# LMP2011basedV2.net
KiCad netlist of a schematic drawn in EAGLE
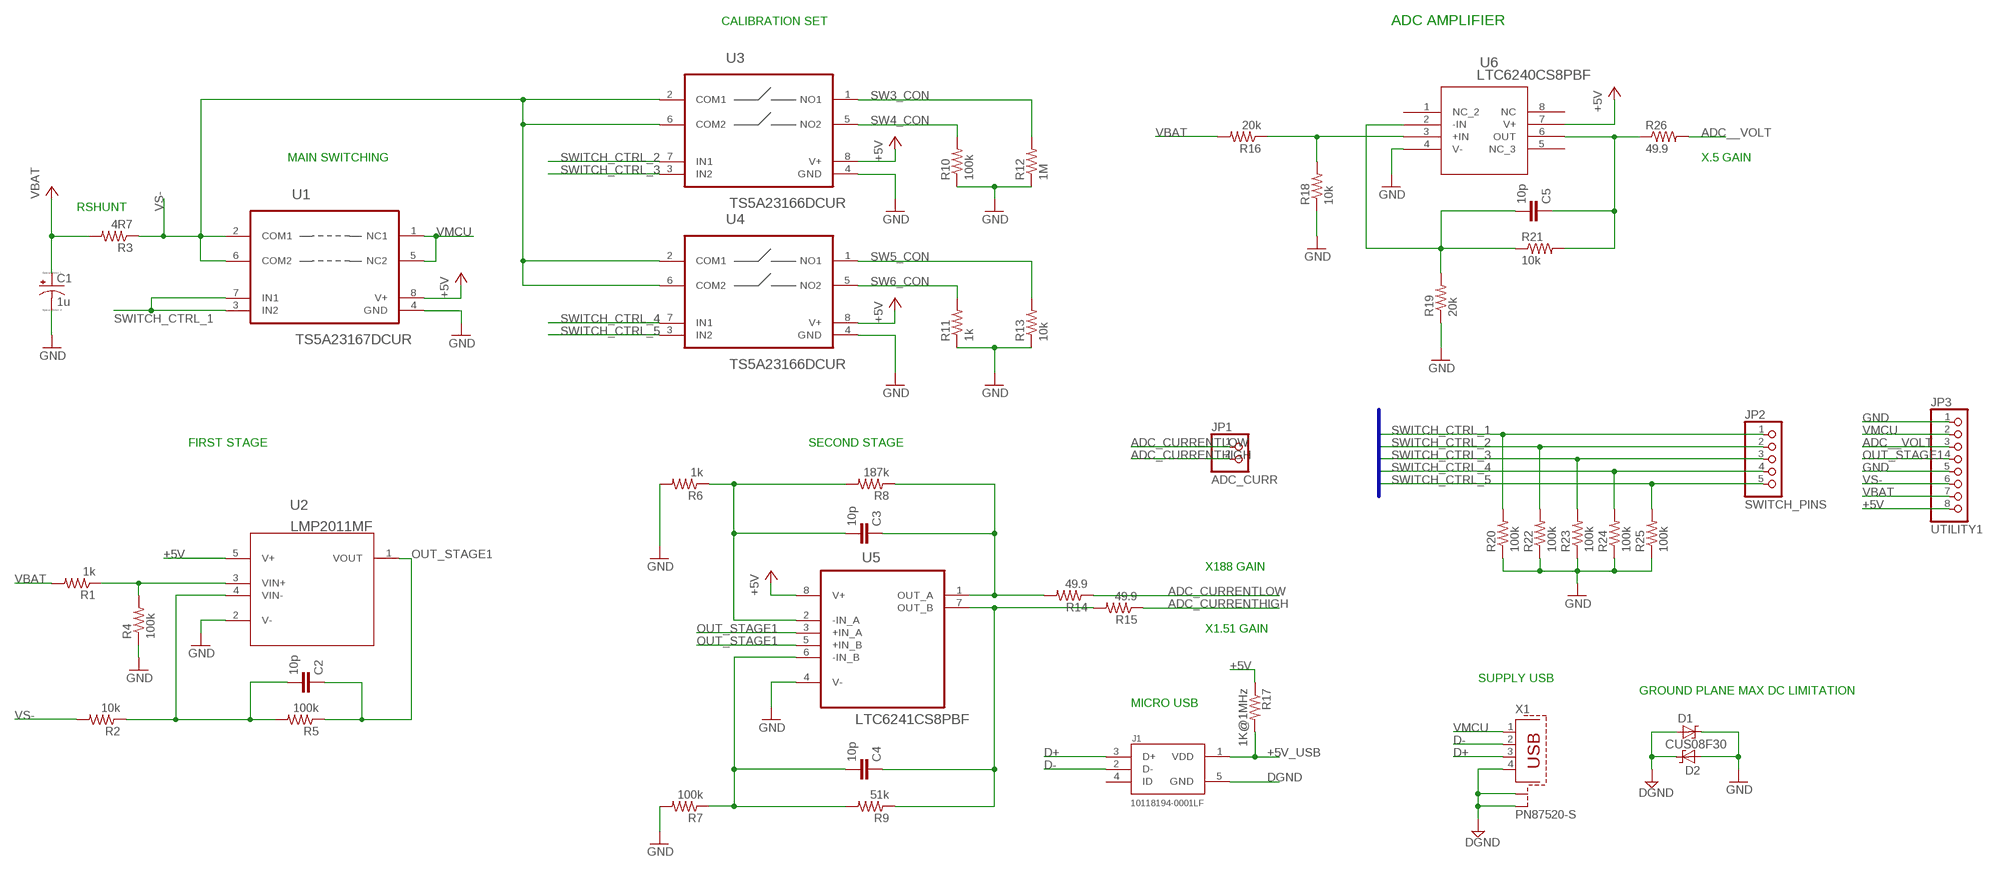
[diagram p0: schematic, sheet 1]

(export (version "E")
  (design (tool "Eeschema 10.0.6"))
  (components
    (comp (ref "C1")
      (value "1u")
      (footprint "eagle-import:PANASONIC_B")
      (libsource (lib "eagle-import") (part "CPOL-USB"))
    )
    (comp (ref "C2")
      (value "10p")
      (footprint "eagle-import:C0805")
      (libsource (lib "eagle-import") (part "C-EUC0805"))
    )
    (comp (ref "C3")
      (value "10p")
      (footprint "eagle-import:C0805")
      (libsource (lib "eagle-import") (part "C-EUC0805"))
    )
    (comp (ref "C4")
      (value "10p")
      (footprint "eagle-import:C0805")
      (libsource (lib "eagle-import") (part "C-EUC0805"))
    )
    (comp (ref "C5")
      (value "10p")
      (footprint "eagle-import:C0805")
      (libsource (lib "eagle-import") (part "C-EUC0805"))
    )
    (comp (ref "D1")
      (value "CUS08F30")
      (footprint "eagle-import:SOD323")
      (fields (field (name "MF") "TOSHIBA"))
      (libsource (lib "eagle-import") (part "CUS08F30"))
    )
    (comp (ref "D2")
      (value "CUS08F30")
      (footprint "eagle-import:SOD323")
      (fields (field (name "MF") "TOSHIBA"))
      (libsource (lib "eagle-import") (part "CUS08F30"))
    )
    (comp (ref "J1")
      (value "10118194-0001LF")
      (footprint "eagle-import:FRAMATOME_10118194-0001LF")
      (fields (field (name "MF") "Amphenol"))
      (libsource (lib "eagle-import") (part "10118194-0001LF"))
    )
    (comp (ref "JP1")
      (value "ADC_CURR")
      (footprint "eagle-import:1X02")
      (libsource (lib "eagle-import") (part "PINHD-1X2"))
    )
    (comp (ref "JP2")
      (value "SWITCH_PINS")
      (footprint "eagle-import:1X05")
      (libsource (lib "eagle-import") (part "PINHD-1X5"))
    )
    (comp (ref "JP3")
      (value "UTILITY1")
      (footprint "eagle-import:1X08")
      (libsource (lib "eagle-import") (part "PINHD-1X8"))
    )
    (comp (ref "R1")
      (value "1k")
      (footprint "eagle-import:R0805")
      (libsource (lib "eagle-import") (part "R-US_R0805"))
    )
    (comp (ref "R2")
      (value "10k")
      (footprint "eagle-import:R0805")
      (libsource (lib "eagle-import") (part "R-US_R0805"))
    )
    (comp (ref "R3")
      (value "4R7")
      (footprint "eagle-import:R0805")
      (libsource (lib "eagle-import") (part "R-US_R0805"))
    )
    (comp (ref "R4")
      (value "100k")
      (footprint "eagle-import:R0805")
      (libsource (lib "eagle-import") (part "R-US_R0805"))
    )
    (comp (ref "R5")
      (value "100k")
      (footprint "eagle-import:R0805")
      (libsource (lib "eagle-import") (part "R-US_R0805"))
    )
    (comp (ref "R6")
      (value "1k")
      (footprint "eagle-import:R0805")
      (libsource (lib "eagle-import") (part "R-US_R0805"))
    )
    (comp (ref "R7")
      (value "100k")
      (footprint "eagle-import:R0805")
      (libsource (lib "eagle-import") (part "R-US_R0805"))
    )
    (comp (ref "R8")
      (value "187k")
      (footprint "eagle-import:R0805")
      (libsource (lib "eagle-import") (part "R-US_R0805"))
    )
    (comp (ref "R9")
      (value "51k")
      (footprint "eagle-import:R0805")
      (libsource (lib "eagle-import") (part "R-US_R0805"))
    )
    (comp (ref "R10")
      (value "100k")
      (footprint "eagle-import:R0805")
      (libsource (lib "eagle-import") (part "R-US_R0805"))
    )
    (comp (ref "R11")
      (value "1k")
      (footprint "eagle-import:R0805")
      (libsource (lib "eagle-import") (part "R-US_R0805"))
    )
    (comp (ref "R12")
      (value "1M")
      (footprint "eagle-import:R0805")
      (libsource (lib "eagle-import") (part "R-US_R0805"))
    )
    (comp (ref "R13")
      (value "10k")
      (footprint "eagle-import:R0805")
      (libsource (lib "eagle-import") (part "R-US_R0805"))
    )
    (comp (ref "R14")
      (value "49.9")
      (footprint "eagle-import:R0805")
      (libsource (lib "eagle-import") (part "R-US_R0805"))
    )
    (comp (ref "R15")
      (value "49.9")
      (footprint "eagle-import:R0805")
      (libsource (lib "eagle-import") (part "R-US_R0805"))
    )
    (comp (ref "R16")
      (value "20k")
      (footprint "eagle-import:R0805")
      (libsource (lib "eagle-import") (part "R-US_R0805"))
    )
    (comp (ref "R17")
      (value "1K@1MHz")
      (footprint "eagle-import:R0805")
      (libsource (lib "eagle-import") (part "R-US_R0805"))
    )
    (comp (ref "R18")
      (value "10k")
      (footprint "eagle-import:R0805")
      (libsource (lib "eagle-import") (part "R-US_R0805"))
    )
    (comp (ref "R19")
      (value "20k")
      (footprint "eagle-import:R0805")
      (libsource (lib "eagle-import") (part "R-US_R0805"))
    )
    (comp (ref "R20")
      (value "100k")
      (footprint "eagle-import:R0805")
      (libsource (lib "eagle-import") (part "R-US_R0805"))
    )
    (comp (ref "R21")
      (value "10k")
      (footprint "eagle-import:R0805")
      (libsource (lib "eagle-import") (part "R-US_R0805"))
    )
    (comp (ref "R22")
      (value "100k")
      (footprint "eagle-import:R0805")
      (libsource (lib "eagle-import") (part "R-US_R0805"))
    )
    (comp (ref "R23")
      (value "100k")
      (footprint "eagle-import:R0805")
      (libsource (lib "eagle-import") (part "R-US_R0805"))
    )
    (comp (ref "R24")
      (value "100k")
      (footprint "eagle-import:R0805")
      (libsource (lib "eagle-import") (part "R-US_R0805"))
    )
    (comp (ref "R25")
      (value "100k")
      (footprint "eagle-import:R0805")
      (libsource (lib "eagle-import") (part "R-US_R0805"))
    )
    (comp (ref "R26")
      (value "49.9")
      (footprint "eagle-import:R0603")
      (libsource (lib "eagle-import") (part "R-US_R0603"))
    )
    (comp (ref "U1")
      (value "TS5A23167DCUR")
      (footprint "eagle-import:SOP50P310X90-8N")
      (fields (field (name "MF") "Texas Instruments"))
      (libsource (lib "eagle-import") (part "TS5A23167DCUR"))
    )
    (comp (ref "U2")
      (value "LMP2011MF")
      (footprint "eagle-import:SOT95P285X120-5N")
      (fields
        (field (name "DIGI-KEY_PART_NUMBER") "LMP2011MF/NOPBCT-ND")
        (field (name "MF") "Texas Instruments")
        (field (name "MP") "LMP2011MF/NOPB")
      )
      (libsource (lib "eagle-import") (part "LMP2011MF"))
    )
    (comp (ref "U3")
      (value "TS5A23166DCUR")
      (footprint "eagle-import:SOP50P310X90-8N")
      (fields (field (name "MF") "Texas Instruments"))
      (libsource (lib "eagle-import") (part "TS5A23166DCUR"))
    )
    (comp (ref "U4")
      (value "TS5A23166DCUR")
      (footprint "eagle-import:SOP50P310X90-8N")
      (fields (field (name "MF") "Texas Instruments"))
      (libsource (lib "eagle-import") (part "TS5A23166DCUR"))
    )
    (comp (ref "U5")
      (value "LTC6241CS8PBF")
      (footprint "eagle-import:SOIC127P600X175-8N")
      (fields (field (name "MF") "Linear Technology") (field (name "MP") "LTC6241CS8#PBF"))
      (libsource (lib "eagle-import") (part "LTC6241CS8PBF"))
    )
    (comp (ref "U6")
      (value "LTC6240CS8PBF")
      (footprint "eagle-import:SO-8_S")
      (fields (field (name "MF") "Linear Technology") (field (name "MP") "LTC6240CS8#PBF"))
      (libsource (lib "eagle-import") (part "LTC6240CS8PBF"))
    )
    (comp (ref "X1")
      (value "PN87520-S")
      (footprint "eagle-import:PN87520-S")
      (libsource (lib "eagle-import") (part "PN87520-S"))
    )
  )
  (nets
    (net (code "1") (name "+5V") (class "Default")
      (node (ref "JP3") (pin "8") (pinfunction "8_8") (pintype "passive"))
      (node (ref "R17") (pin "1") (pinfunction "1_1") (pintype "passive"))
      (node (ref "U1") (pin "8") (pinfunction "V+_8") (pintype "power_in"))
      (node (ref "U2") (pin "5") (pinfunction "V+_5") (pintype "power_in"))
      (node (ref "U3") (pin "8") (pinfunction "V+_8") (pintype "power_in"))
      (node (ref "U4") (pin "8") (pinfunction "V+_8") (pintype "power_in"))
      (node (ref "U5") (pin "8") (pinfunction "V+_8") (pintype "power_in"))
      (node (ref "U6") (pin "7") (pinfunction "V+_7") (pintype "power_in"))
    )
    (net (code "2") (name "/+5V_USB") (class "Default")
      (node (ref "J1") (pin "1") (pinfunction "VDD_1") (pintype "power_in"))
      (node (ref "R17") (pin "2") (pinfunction "2_2") (pintype "passive"))
    )
    (net (code "3") (name "/ADC_CURRENTHIGH") (class "Default")
      (node (ref "JP1") (pin "2") (pinfunction "2_2") (pintype "passive"))
      (node (ref "R15") (pin "1") (pinfunction "1_1") (pintype "passive"))
    )
    (net (code "4") (name "/ADC_CURRENTLOW") (class "Default")
      (node (ref "JP1") (pin "1") (pinfunction "1_1") (pintype "passive"))
      (node (ref "R14") (pin "1") (pinfunction "1_1") (pintype "passive"))
    )
    (net (code "5") (name "/ADC__VOLT") (class "Default")
      (node (ref "JP3") (pin "3") (pinfunction "3_3") (pintype "passive"))
      (node (ref "R26") (pin "2") (pinfunction "2_2") (pintype "passive"))
    )
    (net (code "6") (name "/D+") (class "Default")
      (node (ref "J1") (pin "3") (pinfunction "D+_3") (pintype "bidirectional"))
      (node (ref "X1") (pin "3") (pinfunction "3_3") (pintype "passive"))
    )
    (net (code "7") (name "/D-") (class "Default")
      (node (ref "J1") (pin "2") (pinfunction "D-_2") (pintype "bidirectional"))
      (node (ref "X1") (pin "2") (pinfunction "2_2") (pintype "passive"))
    )
    (net (code "8") (name "/OUT_STAGE1") (class "Default")
      (node (ref "C2") (pin "1") (pinfunction "1_1") (pintype "passive"))
      (node (ref "JP3") (pin "4") (pinfunction "4_4") (pintype "passive"))
      (node (ref "R5") (pin "1") (pinfunction "1_1") (pintype "passive"))
      (node (ref "U2") (pin "1") (pinfunction "VOUT_1") (pintype "output"))
      (node (ref "U5") (pin "3") (pinfunction "+IN_A_3") (pintype "input"))
      (node (ref "U5") (pin "5") (pinfunction "+IN_B_5") (pintype "input"))
    )
    (net (code "9") (name "/SW3_CON") (class "Default")
      (node (ref "R12") (pin "2") (pinfunction "2_2") (pintype "passive"))
      (node (ref "U3") (pin "1") (pinfunction "NO1_1") (pintype "bidirectional"))
    )
    (net (code "10") (name "/SW4_CON") (class "Default")
      (node (ref "R10") (pin "2") (pinfunction "2_2") (pintype "passive"))
      (node (ref "U3") (pin "5") (pinfunction "NO2_5") (pintype "bidirectional"))
    )
    (net (code "11") (name "/SW5_CON") (class "Default")
      (node (ref "R13") (pin "2") (pinfunction "2_2") (pintype "passive"))
      (node (ref "U4") (pin "1") (pinfunction "NO1_1") (pintype "bidirectional"))
    )
    (net (code "12") (name "/SW6_CON") (class "Default")
      (node (ref "R11") (pin "2") (pinfunction "2_2") (pintype "passive"))
      (node (ref "U4") (pin "5") (pinfunction "NO2_5") (pintype "bidirectional"))
    )
    (net (code "13") (name "/SWITCH_CTRL_1") (class "Default")
      (node (ref "JP2") (pin "1") (pinfunction "1_1") (pintype "passive"))
      (node (ref "R20") (pin "2") (pinfunction "2_2") (pintype "passive"))
      (node (ref "U1") (pin "3") (pinfunction "IN2_3") (pintype "input"))
      (node (ref "U1") (pin "7") (pinfunction "IN1_7") (pintype "input"))
    )
    (net (code "14") (name "/SWITCH_CTRL_2") (class "Default")
      (node (ref "JP2") (pin "2") (pinfunction "2_2") (pintype "passive"))
      (node (ref "R22") (pin "2") (pinfunction "2_2") (pintype "passive"))
      (node (ref "U3") (pin "7") (pinfunction "IN1_7") (pintype "input"))
    )
    (net (code "15") (name "/SWITCH_CTRL_3") (class "Default")
      (node (ref "JP2") (pin "3") (pinfunction "3_3") (pintype "passive"))
      (node (ref "R23") (pin "2") (pinfunction "2_2") (pintype "passive"))
      (node (ref "U3") (pin "3") (pinfunction "IN2_3") (pintype "input"))
    )
    (net (code "16") (name "/SWITCH_CTRL_4") (class "Default")
      (node (ref "JP2") (pin "4") (pinfunction "4_4") (pintype "passive"))
      (node (ref "R24") (pin "2") (pinfunction "2_2") (pintype "passive"))
      (node (ref "U4") (pin "7") (pinfunction "IN1_7") (pintype "input"))
    )
    (net (code "17") (name "/SWITCH_CTRL_5") (class "Default")
      (node (ref "JP2") (pin "5") (pinfunction "5_5") (pintype "passive"))
      (node (ref "R25") (pin "2") (pinfunction "2_2") (pintype "passive"))
      (node (ref "U4") (pin "3") (pinfunction "IN2_3") (pintype "input"))
    )
    (net (code "18") (name "/VMCU") (class "Default")
      (node (ref "JP3") (pin "2") (pinfunction "2_2") (pintype "passive"))
      (node (ref "U1") (pin "1") (pinfunction "NC1_1") (pintype "bidirectional"))
      (node (ref "U1") (pin "5") (pinfunction "NC2_5") (pintype "bidirectional"))
      (node (ref "X1") (pin "1") (pinfunction "1_1") (pintype "passive"))
    )
    (net (code "19") (name "/VS-") (class "Default")
      (node (ref "JP3") (pin "6") (pinfunction "6_6") (pintype "passive"))
      (node (ref "R2") (pin "2") (pinfunction "2_2") (pintype "passive"))
      (node (ref "R3") (pin "1") (pinfunction "1_1") (pintype "passive"))
      (node (ref "U1") (pin "2") (pinfunction "COM1_2") (pintype "bidirectional"))
      (node (ref "U1") (pin "6") (pinfunction "COM2_6") (pintype "bidirectional"))
      (node (ref "U3") (pin "2") (pinfunction "COM1_2") (pintype "bidirectional"))
      (node (ref "U3") (pin "6") (pinfunction "COM2_6") (pintype "bidirectional"))
      (node (ref "U4") (pin "2") (pinfunction "COM1_2") (pintype "bidirectional"))
      (node (ref "U4") (pin "6") (pinfunction "COM2_6") (pintype "bidirectional"))
    )
    (net (code "20") (name "DGND") (class "Default")
      (node (ref "D1") (pin "A") (pinfunction "A_A") (pintype "passive"))
      (node (ref "D2") (pin "C") (pinfunction "C_C") (pintype "passive"))
      (node (ref "J1") (pin "5") (pinfunction "GND_5") (pintype "power_in"))
      (node (ref "X1") (pin "4") (pinfunction "4_4") (pintype "passive"))
      (node (ref "X1") (pin "S1") (pinfunction "S1_S1") (pintype "passive"))
      (node (ref "X1") (pin "S2") (pinfunction "S2_S2") (pintype "passive"))
    )
    (net (code "21") (name "GND") (class "Default")
      (node (ref "C1") (pin "-") (pinfunction "-_-") (pintype "passive"))
      (node (ref "D1") (pin "C") (pinfunction "C_C") (pintype "passive"))
      (node (ref "D2") (pin "A") (pinfunction "A_A") (pintype "passive"))
      (node (ref "JP3") (pin "1") (pinfunction "1_1") (pintype "passive"))
      (node (ref "JP3") (pin "5") (pinfunction "5_5") (pintype "passive"))
      (node (ref "R10") (pin "1") (pinfunction "1_1") (pintype "passive"))
      (node (ref "R11") (pin "1") (pinfunction "1_1") (pintype "passive"))
      (node (ref "R12") (pin "1") (pinfunction "1_1") (pintype "passive"))
      (node (ref "R13") (pin "1") (pinfunction "1_1") (pintype "passive"))
      (node (ref "R18") (pin "1") (pinfunction "1_1") (pintype "passive"))
      (node (ref "R19") (pin "1") (pinfunction "1_1") (pintype "passive"))
      (node (ref "R20") (pin "1") (pinfunction "1_1") (pintype "passive"))
      (node (ref "R22") (pin "1") (pinfunction "1_1") (pintype "passive"))
      (node (ref "R23") (pin "1") (pinfunction "1_1") (pintype "passive"))
      (node (ref "R24") (pin "1") (pinfunction "1_1") (pintype "passive"))
      (node (ref "R25") (pin "1") (pinfunction "1_1") (pintype "passive"))
      (node (ref "R4") (pin "1") (pinfunction "1_1") (pintype "passive"))
      (node (ref "R6") (pin "2") (pinfunction "2_2") (pintype "passive"))
      (node (ref "R7") (pin "2") (pinfunction "2_2") (pintype "passive"))
      (node (ref "U1") (pin "4") (pinfunction "GND_4") (pintype "passive"))
      (node (ref "U2") (pin "2") (pinfunction "V-_2") (pintype "power_in"))
      (node (ref "U3") (pin "4") (pinfunction "GND_4") (pintype "passive"))
      (node (ref "U4") (pin "4") (pinfunction "GND_4") (pintype "passive"))
      (node (ref "U5") (pin "4") (pinfunction "V-_4") (pintype "power_in"))
      (node (ref "U6") (pin "4") (pinfunction "V-_4") (pintype "power_in"))
    )
    (net (code "22") (name "Net-(U2-VIN+)") (class "Default")
      (node (ref "R1") (pin "1") (pinfunction "1_1") (pintype "passive"))
      (node (ref "R4") (pin "2") (pinfunction "2_2") (pintype "passive"))
      (node (ref "U2") (pin "3") (pinfunction "VIN+_3") (pintype "input"))
    )
    (net (code "23") (name "Net-(U2-VIN-)") (class "Default")
      (node (ref "C2") (pin "2") (pinfunction "2_2") (pintype "passive"))
      (node (ref "R2") (pin "1") (pinfunction "1_1") (pintype "passive"))
      (node (ref "R5") (pin "2") (pinfunction "2_2") (pintype "passive"))
      (node (ref "U2") (pin "4") (pinfunction "VIN-_4") (pintype "input"))
    )
    (net (code "24") (name "Net-(U5--IN_A)") (class "Default")
      (node (ref "C3") (pin "2") (pinfunction "2_2") (pintype "passive"))
      (node (ref "R6") (pin "1") (pinfunction "1_1") (pintype "passive"))
      (node (ref "R8") (pin "2") (pinfunction "2_2") (pintype "passive"))
      (node (ref "U5") (pin "2") (pinfunction "-IN_A_2") (pintype "input"))
    )
    (net (code "25") (name "Net-(U5--IN_B)") (class "Default")
      (node (ref "C4") (pin "2") (pinfunction "2_2") (pintype "passive"))
      (node (ref "R7") (pin "1") (pinfunction "1_1") (pintype "passive"))
      (node (ref "R9") (pin "2") (pinfunction "2_2") (pintype "passive"))
      (node (ref "U5") (pin "6") (pinfunction "-IN_B_6") (pintype "input"))
    )
    (net (code "26") (name "Net-(U5-OUT_A)") (class "Default")
      (node (ref "C3") (pin "1") (pinfunction "1_1") (pintype "passive"))
      (node (ref "R14") (pin "2") (pinfunction "2_2") (pintype "passive"))
      (node (ref "R8") (pin "1") (pinfunction "1_1") (pintype "passive"))
      (node (ref "U5") (pin "1") (pinfunction "OUT_A_1") (pintype "output"))
    )
    (net (code "27") (name "Net-(U5-OUT_B)") (class "Default")
      (node (ref "C4") (pin "1") (pinfunction "1_1") (pintype "passive"))
      (node (ref "R15") (pin "2") (pinfunction "2_2") (pintype "passive"))
      (node (ref "R9") (pin "1") (pinfunction "1_1") (pintype "passive"))
      (node (ref "U5") (pin "7") (pinfunction "OUT_B_7") (pintype "output"))
    )
    (net (code "28") (name "Net-(U6-+IN)") (class "Default")
      (node (ref "R16") (pin "1") (pinfunction "1_1") (pintype "passive"))
      (node (ref "R18") (pin "2") (pinfunction "2_2") (pintype "passive"))
      (node (ref "U6") (pin "3") (pinfunction "+IN_3") (pintype "input"))
    )
    (net (code "29") (name "Net-(U6--IN)") (class "Default")
      (node (ref "C5") (pin "2") (pinfunction "2_2") (pintype "passive"))
      (node (ref "R19") (pin "2") (pinfunction "2_2") (pintype "passive"))
      (node (ref "R21") (pin "1") (pinfunction "1_1") (pintype "passive"))
      (node (ref "U6") (pin "2") (pinfunction "-IN_2") (pintype "input"))
    )
    (net (code "30") (name "Net-(U6-OUT)") (class "Default")
      (node (ref "C5") (pin "1") (pinfunction "1_1") (pintype "passive"))
      (node (ref "R21") (pin "2") (pinfunction "2_2") (pintype "passive"))
      (node (ref "R26") (pin "1") (pinfunction "1_1") (pintype "passive"))
      (node (ref "U6") (pin "6") (pinfunction "OUT_6") (pintype "output"))
    )
    (net (code "31") (name "VBAT") (class "Default")
      (node (ref "C1") (pin "+") (pinfunction "+_+") (pintype "passive"))
      (node (ref "JP3") (pin "7") (pinfunction "7_7") (pintype "passive"))
      (node (ref "R1") (pin "2") (pinfunction "2_2") (pintype "passive"))
      (node (ref "R16") (pin "2") (pinfunction "2_2") (pintype "passive"))
      (node (ref "R3") (pin "2") (pinfunction "2_2") (pintype "passive"))
    )
    (net (code "32") (name "unconnected-(J1-ID-Pad4)") (class "Default")
      (node (ref "J1") (pin "4") (pinfunction "ID_4") (pintype "passive"))
    )
    (net (code "33") (name "unconnected-(U6-NC-Pad8)") (class "Default")
      (node (ref "U6") (pin "8") (pinfunction "NC_8") (pintype "no_connect"))
    )
    (net (code "34") (name "unconnected-(U6-NC_2-Pad1)") (class "Default")
      (node (ref "U6") (pin "1") (pinfunction "NC_2_1") (pintype "no_connect"))
    )
    (net (code "35") (name "unconnected-(U6-NC_3-Pad5)") (class "Default")
      (node (ref "U6") (pin "5") (pinfunction "NC_3_5") (pintype "no_connect"))
    )
  )
)
